# DS157-1_0-C.net
KiCad netlist of a schematic drawn in Altium Designer
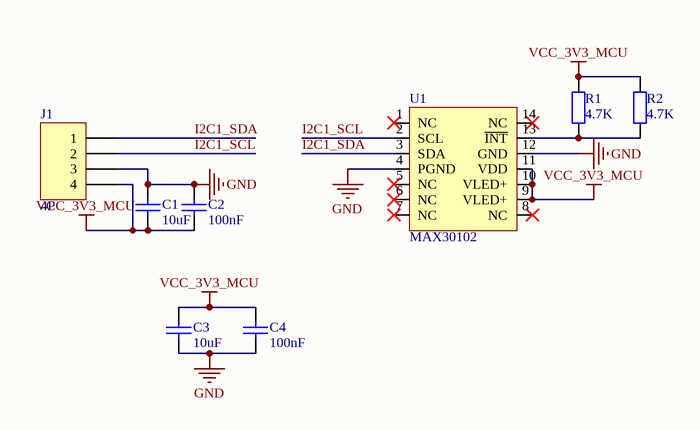
[diagram p0: DS157-1.0-C心率传感器.SchDoc]

(export (version "E")
  (design (tool "Eeschema 10.0.6"))
  (components
    (comp (ref "C1")
      (value "10uF")
      (footprint "0603CAP")
      (description "贴片电容")
      (fields (field (name "Comment") "SMDCAP00016"))
      (libsource (lib "AD_SCH") (part "MLCC 10uF 50V ±10％ 0603"))
    )
    (comp (ref "C2")
      (value "100nF")
      (footprint "0603CAP")
      (description "贴片电容")
      (fields (field (name "Comment") "SMDCAP00013"))
      (libsource (lib "AD_SCH") (part "MLCC 100nF 50V ±10％ 0603"))
    )
    (comp (ref "C3")
      (value "10uF")
      (footprint "0603CAP")
      (description "贴片电容")
      (fields (field (name "Comment") "SMDCAP00016"))
      (libsource (lib "AD_SCH") (part "MLCC 10uF 50V ±10％ 0603"))
    )
    (comp (ref "C4")
      (value "100nF")
      (footprint "0603CAP")
      (description "贴片电容")
      (fields (field (name "Comment") "SMDCAP00013"))
      (libsource (lib "AD_SCH") (part "MLCC 100nF 50V ±10％ 0603"))
    )
    (comp (ref "J1")
      (value "4P")
      (footprint "SIP4")
      (description "单排母座")
      (fields (field (name "Comment") "SL000000047"))
      (libsource (lib "AD_SCH") (part "DIP4 单排母座 间距2.54mm 铜"))
    )
    (comp (ref "R1")
      (value "4.7K")
      (footprint "0603RES")
      (description "贴片电阻")
      (fields (field (name "Comment") "SMDRES00047"))
      (libsource (lib "AD_SCH") (part "Chip 4.7K 1/16W ±1％ 0603"))
    )
    (comp (ref "R2")
      (value "4.7K")
      (footprint "0603RES")
      (description "贴片电阻")
      (fields (field (name "Comment") "SMDRES00047"))
      (libsource (lib "AD_SCH") (part "Chip 4.7K 1/16W ±1％ 0603"))
    )
    (comp (ref "U1") (value "MAX30102") (footprint "OESIP-14") (libsource (lib "AD_SCH") (part "MAX30102")))
  )
  (nets
    (net (code "1") (name "/I2C1_SCL") (class "Default")
      (node (ref "J1") (pin "2") (pinfunction "2_2") (pintype "passive"))
      (node (ref "U1") (pin "2") (pinfunction "SCL_2") (pintype "passive"))
    )
    (net (code "2") (name "/I2C1_SDA") (class "Default")
      (node (ref "J1") (pin "1") (pinfunction "1_1") (pintype "passive"))
      (node (ref "U1") (pin "3") (pinfunction "SDA_3") (pintype "passive"))
    )
    (net (code "3") (name "GND") (class "Default")
      (node (ref "C1") (pin "2") (pinfunction "2_2") (pintype "passive"))
      (node (ref "C2") (pin "2") (pinfunction "2_2") (pintype "passive"))
      (node (ref "C3") (pin "1") (pinfunction "1_1") (pintype "passive"))
      (node (ref "C4") (pin "1") (pinfunction "1_1") (pintype "passive"))
      (node (ref "J1") (pin "3") (pinfunction "3_3") (pintype "passive"))
      (node (ref "U1") (pin "12") (pinfunction "GND_12") (pintype "passive"))
      (node (ref "U1") (pin "4") (pinfunction "PGND_4") (pintype "passive"))
    )
    (net (code "4") (name "Net-(U1-INT)") (class "Default")
      (node (ref "R1") (pin "1") (pinfunction "1_1") (pintype "passive"))
      (node (ref "R2") (pin "1") (pinfunction "1_1") (pintype "passive"))
      (node (ref "U1") (pin "13") (pinfunction "INT_13") (pintype "passive"))
    )
    (net (code "5") (name "VCC_3V3_MCU") (class "Default")
      (node (ref "C1") (pin "1") (pinfunction "1_1") (pintype "passive"))
      (node (ref "C2") (pin "1") (pinfunction "1_1") (pintype "passive"))
      (node (ref "C3") (pin "2") (pinfunction "2_2") (pintype "passive"))
      (node (ref "C4") (pin "2") (pinfunction "2_2") (pintype "passive"))
      (node (ref "J1") (pin "4") (pinfunction "4_4") (pintype "passive"))
      (node (ref "R1") (pin "2") (pinfunction "2_2") (pintype "passive"))
      (node (ref "R2") (pin "2") (pinfunction "2_2") (pintype "passive"))
      (node (ref "U1") (pin "10") (pinfunction "VLED+_10") (pintype "passive"))
      (node (ref "U1") (pin "11") (pinfunction "VDD_11") (pintype "passive"))
      (node (ref "U1") (pin "9") (pinfunction "VLED+_9") (pintype "passive"))
    )
    (net (code "6") (name "unconnected-(U1-NC-Pad1)") (class "Default")
      (node (ref "U1") (pin "1") (pinfunction "NC_1") (pintype "passive+no_connect"))
    )
    (net (code "7") (name "unconnected-(U1-NC-Pad5)") (class "Default")
      (node (ref "U1") (pin "5") (pinfunction "NC_5") (pintype "passive+no_connect"))
    )
    (net (code "8") (name "unconnected-(U1-NC-Pad6)") (class "Default")
      (node (ref "U1") (pin "6") (pinfunction "NC_6") (pintype "passive+no_connect"))
    )
    (net (code "9") (name "unconnected-(U1-NC-Pad7)") (class "Default")
      (node (ref "U1") (pin "7") (pinfunction "NC_7") (pintype "passive+no_connect"))
    )
    (net (code "10") (name "unconnected-(U1-NC-Pad8)") (class "Default")
      (node (ref "U1") (pin "8") (pinfunction "NC_8") (pintype "passive+no_connect"))
    )
    (net (code "11") (name "unconnected-(U1-NC-Pad14)") (class "Default")
      (node (ref "U1") (pin "14") (pinfunction "NC_14") (pintype "passive+no_connect"))
    )
  )
)
